# Headlights.net
KiCad netlist of a schematic drawn in EAGLE
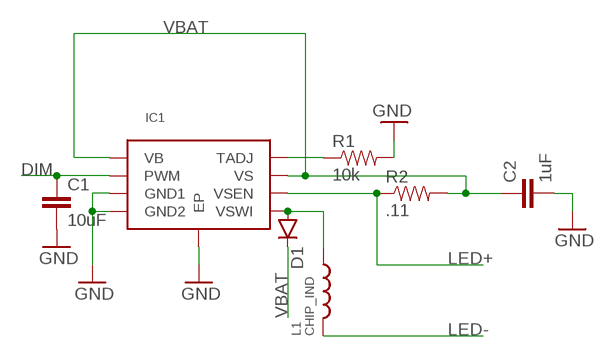
[diagram p0: schematic, sheet 1]

(export (version "E")
  (design (tool "Eeschema 10.0.6"))
  (components
    (comp (ref "C1")
      (value "10uF")
      (footprint "eagle-import:0805-CAP")
      (libsource (lib "eagle-import") (part "10UF10V10%(0805)"))
    )
    (comp (ref "C2")
      (value "1uF")
      (footprint "eagle-import:1206-CAP")
      (libsource (lib "eagle-import") (part "2.2UF50V10%(1206)"))
    )
    (comp (ref "D1")
      (value "DIODESMA-ALT")
      (footprint "eagle-import:SMA-DIODE_ALT")
      (libsource (lib "eagle-import") (part "DIODESMA-ALT"))
    )
    (comp (ref "IC1")
      (value "ILD6150_LED_DRIVER")
      (footprint "eagle-import:PG-DSO-8-27")
      (libsource (lib "eagle-import") (part "ILD6150_LED_DRIVER"))
    )
    (comp (ref "L1")
      (value "CHIP_IND")
      (footprint "eagle-import:12X12MM_IND")
      (libsource (lib "eagle-import") (part "CHIP_IND"))
    )
    (comp (ref "R1")
      (value "10k")
      (footprint "eagle-import:0805")
      (libsource (lib "eagle-import") (part "0.3OHM-1/8W-1%(0805)"))
    )
    (comp (ref "R2")
      (value ".11")
      (footprint "eagle-import:R2010")
      (libsource (lib "eagle-import") (part "0.11OHM1/2W1%(2010)"))
    )
  )
  (nets
    (net (code "1") (name "/DIM") (class "Default")
      (node (ref "C1") (pin "1") (pinfunction "1_1") (pintype "passive"))
      (node (ref "IC1") (pin "P$2") (pinfunction "PWM_P$2") (pintype "bidirectional"))
    )
    (net (code "2") (name "/LED+") (class "Default")
      (node (ref "IC1") (pin "P$6") (pinfunction "VSEN_P$6") (pintype "bidirectional"))
      (node (ref "R2") (pin "1") (pinfunction "1_1") (pintype "passive"))
    )
    (net (code "3") (name "/LED-") (class "Default")
      (node (ref "L1") (pin "P$1") (pinfunction "P$1_P$1") (pintype "bidirectional"))
    )
    (net (code "4") (name "/VBAT") (class "Default")
      (node (ref "C2") (pin "1") (pinfunction "1_1") (pintype "passive"))
      (node (ref "D1") (pin "C") (pinfunction "C_C") (pintype "passive"))
      (node (ref "IC1") (pin "P$1") (pinfunction "VB_P$1") (pintype "bidirectional"))
      (node (ref "IC1") (pin "P$7") (pinfunction "VS_P$7") (pintype "bidirectional"))
      (node (ref "R2") (pin "2") (pinfunction "2_2") (pintype "passive"))
    )
    (net (code "5") (name "GND") (class "Default")
      (node (ref "C1") (pin "2") (pinfunction "2_2") (pintype "passive"))
      (node (ref "C2") (pin "2") (pinfunction "2_2") (pintype "passive"))
      (node (ref "IC1") (pin "P$3") (pinfunction "GND1_P$3") (pintype "bidirectional"))
      (node (ref "IC1") (pin "P$4") (pinfunction "GND2_P$4") (pintype "bidirectional"))
      (node (ref "IC1") (pin "P$9") (pinfunction "EP_P$9") (pintype "bidirectional"))
      (node (ref "R1") (pin "2") (pinfunction "2_2") (pintype "passive"))
    )
    (net (code "6") (name "Net-(IC1-TADJ)") (class "Default")
      (node (ref "IC1") (pin "P$8") (pinfunction "TADJ_P$8") (pintype "bidirectional"))
      (node (ref "R1") (pin "1") (pinfunction "1_1") (pintype "passive"))
    )
    (net (code "7") (name "Net-(IC1-VSWI)") (class "Default")
      (node (ref "D1") (pin "A") (pinfunction "A_A") (pintype "passive"))
      (node (ref "IC1") (pin "P$5") (pinfunction "VSWI_P$5") (pintype "bidirectional"))
      (node (ref "L1") (pin "P$2") (pinfunction "P$2_P$2") (pintype "bidirectional"))
    )
  )
)
